# FTDI.net
KiCad netlist of a schematic drawn in Altium Designer
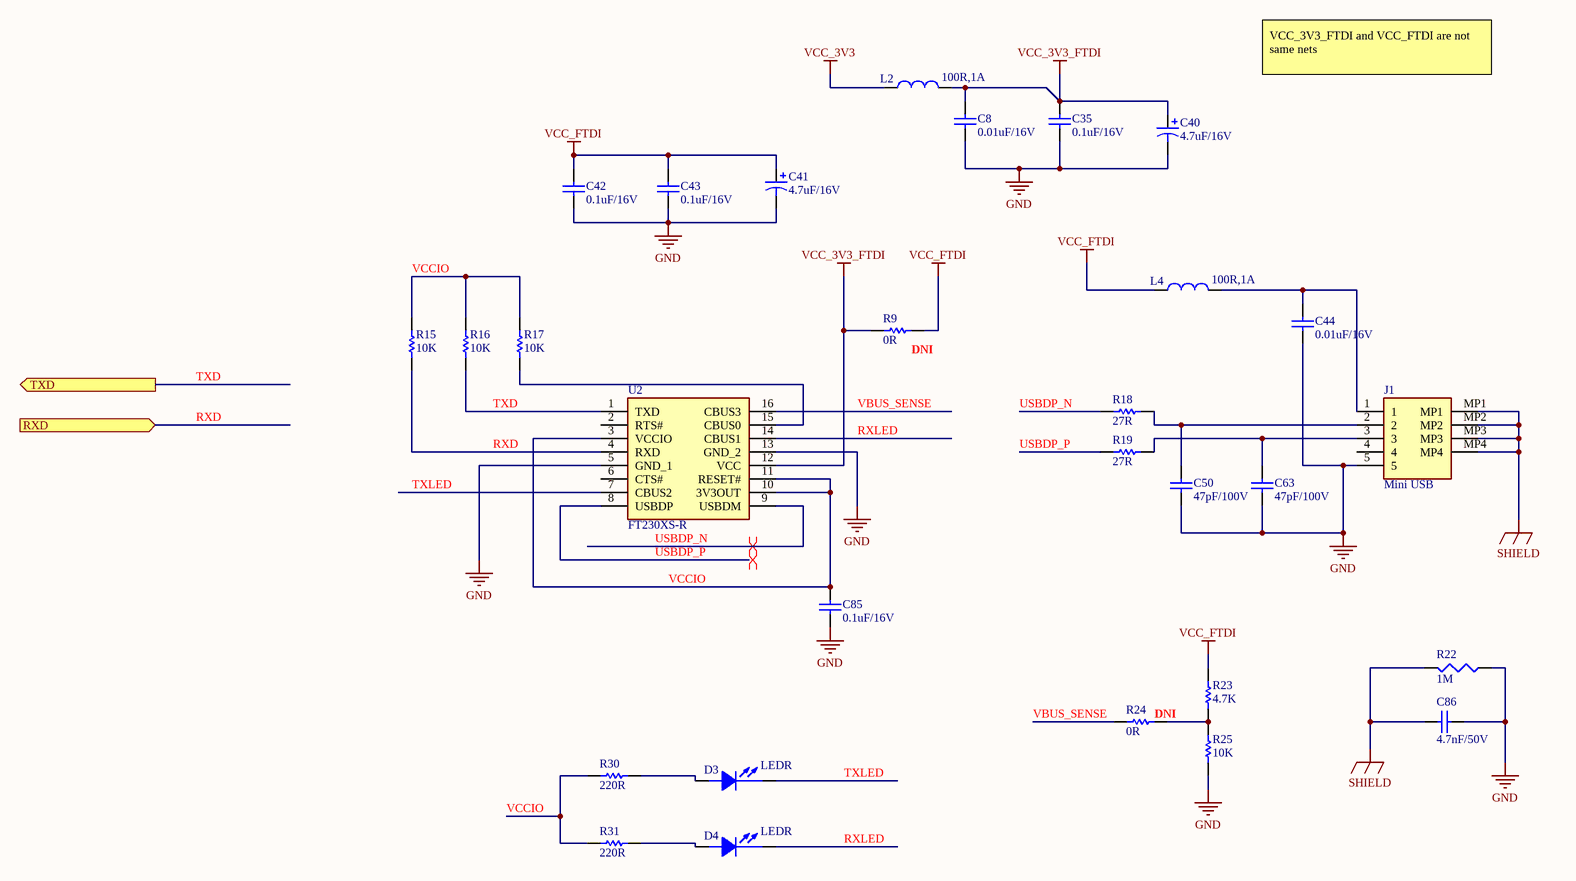
[diagram p0: FTDI.SchDoc]

(export (version "E")
  (design (tool "Eeschema 10.0.6"))
  (components
    (comp (ref "C8")
      (value "0.01uF/16V")
      (footprint "0603C")
      (description "Multilayer Ceramic Capacitors MLCC - SMD/SMT 16V 0.01uF X7R 0603 10% AEC-Q200")
      (fields (field (name "MFR") "KEMET") (field (name "MFR PART NO") "C0603C103K4RECAUTO"))
      (libsource (lib "Miscellaneous Devices") (part "Cap"))
    )
    (comp (ref "C35")
      (value "0.1uF/16V")
      (footprint "0603C")
      (description "Multilayer Ceramic Capacitors MLCC - SMD/SMT 0603 16VDC 0.1uF 10% X7R AEC-Q200")
      (fields (field (name "MFR") "Taiyo Yuden") (field (name "MFR PART NO") "EMK107B7104KAHT"))
      (libsource (lib "Miscellaneous Devices") (part "Cap"))
    )
    (comp (ref "C40")
      (value "4.7uF/16V")
      (footprint "CASE-A")
      (description "Tantalum Capacitors - Solid SMD 16V 4.7uF 1206")
      (fields (field (name "MFR") "KEMET") (field (name "MFR PART NO") "T495A475K016ATA2K0"))
      (libsource (lib "Miscellaneous Devices") (part "Cap Pol1"))
    )
    (comp (ref "C41")
      (value "4.7uF/16V")
      (footprint "CASE-A")
      (description "Tantalum Capacitors - Solid SMD 16V 4.7uF 1206")
      (fields (field (name "MFR") "KEMET") (field (name "MFR PART NO") "T495A475K016ATA2K0"))
      (libsource (lib "Miscellaneous Devices") (part "Cap Pol1"))
    )
    (comp (ref "C42")
      (value "0.1uF/16V")
      (footprint "0603C")
      (description "Multilayer Ceramic Capacitors MLCC - SMD/SMT 0603 16VDC 0.1uF 10% X7R AEC-Q2000")
      (fields (field (name "MFR") "Taiyo Yuden") (field (name "MFR PART NO") "EMK107B7104KAHT"))
      (libsource (lib "Miscellaneous Devices") (part "Cap"))
    )
    (comp (ref "C43")
      (value "0.1uF/16V")
      (footprint "0603C")
      (description "Multilayer Ceramic Capacitors MLCC - SMD/SMT 0603 16VDC 0.1uF 10% X7R AEC-Q2000")
      (fields (field (name "MFR") "Taiyo Yuden") (field (name "MFR PART NO") "EMK107B7104KAHT"))
      (libsource (lib "Miscellaneous Devices") (part "Cap"))
    )
    (comp (ref "C44")
      (value "0.01uF/16V")
      (footprint "0603C")
      (description "Multilayer Ceramic Capacitors MLCC - SMD/SMT 16V 0.01uF X7R 0603 10% AEC-Q200")
      (fields (field (name "MFR") "KEMET") (field (name "MFR PART NO") "C0603C103K4RECAUTO"))
      (libsource (lib "Miscellaneous Devices") (part "Cap"))
    )
    (comp (ref "C50")
      (value "47pF/100V")
      (footprint "0603C")
      (description "Multilayer Ceramic Capacitors MLCC - SMD/SMT 100V 47pF 0603 X8R 20% AEC-Q200")
      (fields (field (name "MFR") "KEMET") (field (name "MFR PART NO") "C0603C470M1HACAUTO"))
      (libsource (lib "Miscellaneous Devices") (part "Cap"))
    )
    (comp (ref "C63")
      (value "47pF/100V")
      (footprint "0603C")
      (description "Multilayer Ceramic Capacitors MLCC - SMD/SMT 100V 47pF 0603 X8R 20% AEC-Q200")
      (fields (field (name "MFR") "KEMET") (field (name "MFR PART NO") "C0603C470M1HACAUTO"))
      (libsource (lib "Miscellaneous Devices") (part "Cap"))
    )
    (comp (ref "C85")
      (value "0.1uF/16V")
      (footprint "0603C")
      (description "Multilayer Ceramic Capacitors MLCC - SMD/SMT 0603 16VDC 0.1uF 10% X7R AEC-Q2000")
      (fields (field (name "MFR") "Taiyo Yuden") (field (name "MFR PART NO") "EMK107B7104KAHT"))
      (libsource (lib "Miscellaneous Devices") (part "Cap"))
    )
    (comp (ref "C86")
      (value "4.7nF/50V")
      (footprint "0603C")
      (description "Multilayer Ceramic Capacitors MLCC - SMD/SMT 50V 4700pF X7R 0603 10% AEC-Q200")
      (fields
        (field (name "MFR PART NO") "C0603C472K5RACAUTO7411")
        (field (name "STOCKIEST PART NO") "80-C0603C472K5RAUTLR")
      )
      (libsource (lib "Myde10") (part "0805_CAP"))
    )
    (comp (ref "D3")
      (value "LEDR")
      (footprint "LED_0603")
      (description "Standard LEDs - SMD Red 631nm 14mcd 5mA")
      (fields
        (field (name "STOCKIEST PART NO") "859-LTSTC193KRKT5A")
        (field (name "MFR PART NO") "LTST-C193KRKT-5A")
      )
      (libsource (lib "de20") (part "LED"))
    )
    (comp (ref "D4")
      (value "LEDR")
      (footprint "LED_0603")
      (description "Standard LEDs - SMD Red 631nm 14mcd 5mA")
      (fields
        (field (name "STOCKIEST PART NO") "859-LTSTC193KRKT5A")
        (field (name "MFR PART NO") "LTST-C193KRKT-5A")
      )
      (libsource (lib "de20") (part "LED"))
    )
    (comp (ref "J1")
      (value "Mini USB")
      (footprint "ProjCLib:10033527-N3112LF")
      (description "USB Connectors M-USB 1X1 B/REC R/A SMT")
      (fields (field (name "MFR") "TE Connectivity") (field (name "MFR PART NO") "1734035-2"))
      (libsource (lib "*") (part "10033527-N3112LF"))
    )
    (comp (ref "L2")
      (value "100R,1A")
      (footprint "0603L")
      (description "Ferrite Beads 100ohms 1A 60mOhms 0603 Ferrite Chip")
      (fields (field (name "MFR") "TDK") (field (name "MFR PART NO") "MPZ1608D101BTA00"))
      (libsource (lib "de20") (part "0805_IND"))
    )
    (comp (ref "L4")
      (value "100R,1A")
      (footprint "0603L")
      (description "Ferrite Beads 100ohms 1A 60mOhms 0603 Ferrite Chip")
      (fields (field (name "MFR") "TDK") (field (name "MFR PART NO") "MPZ1608D101BTA00"))
      (libsource (lib "de20") (part "0805_IND"))
    )
    (comp (ref "R9")
      (value "0R")
      (footprint "0603R")
      (description "Thick Film Resistors - SMD 1/10Watt 0ohms Commercial Use")
      (fields (field (name "MFR") "Vishay / Dale") (field (name "MFR PART NO") "CRCW06030000Z0EAC"))
      (libsource (lib "Miscellaneous Devices") (part "Res1"))
    )
    (comp (ref "R15")
      (value "10K")
      (footprint "0603R")
      (description "Thick Film Resistors - SMD 0603 10Kohms 1% Anti-Sulfur AEC-Q200")
      (fields (field (name "MFR") "ROHM Semiconductor") (field (name "MFR PART NO") "SFR03EZPF1002"))
      (libsource (lib "Miscellaneous Devices") (part "Res1"))
    )
    (comp (ref "R16")
      (value "10K")
      (footprint "0603R")
      (description "Thick Film Resistors - SMD 0603 10Kohms 1% Anti-Sulfur AEC-Q200")
      (fields (field (name "MFR") "ROHM Semiconductor") (field (name "MFR PART NO") "SFR03EZPF1002"))
      (libsource (lib "Miscellaneous Devices") (part "Res1"))
    )
    (comp (ref "R17")
      (value "10K")
      (footprint "0603R")
      (description "Thick Film Resistors - SMD 0603 10Kohms 1% Anti-Sulfur AEC-Q200")
      (fields (field (name "MFR") "ROHM Semiconductor") (field (name "MFR PART NO") "SFR03EZPF1002"))
      (libsource (lib "Miscellaneous Devices") (part "Res1"))
    )
    (comp (ref "R18")
      (value "27R")
      (footprint "0603R")
      (description "Thick Film Resistors - SMD 0603 0.25W 1% 27ohm AEC-Q200")
      (fields (field (name "MFR") "Panasonic") (field (name "MFR PART NO") "ERJ-UP3F27R0V"))
      (libsource (lib "Miscellaneous Devices") (part "Res1"))
    )
    (comp (ref "R19")
      (value "27R")
      (footprint "0603R")
      (description "Thick Film Resistors - SMD 0603 0.25W 1% 27ohm AEC-Q200")
      (fields (field (name "MFR") "Panasonic") (field (name "MFR PART NO") "ERJ-UP3F27R0V"))
      (libsource (lib "Miscellaneous Devices") (part "Res1"))
    )
    (comp (ref "R22")
      (value "1M")
      (footprint "0805R")
      (description "Thick Film Resistors - SMD 0603 0.25W 1% 1Mohm AEC-Q200")
      (fields
        (field (name "MFR PART NO") "ERJ-UP3F1004V")
        (field (name "STOCKIEST PART NO") "667-ERJ-UP3F1004V")
      )
      (libsource (lib "Myde10") (part "0805_RES"))
    )
    (comp (ref "R23")
      (value "4.7K")
      (footprint "0603R")
      (description "Thick Film Resistors - SMD 1/10Watt 4.7Kohms 5% Commercial Use")
      (fields (field (name "MFR") "Vishay / Dale") (field (name "MFR PART NO") "CRCW06034K70JNEAC"))
      (libsource (lib "Miscellaneous Devices") (part "Res1"))
    )
    (comp (ref "R24")
      (value "0R")
      (footprint "0603R")
      (description "Thick Film Resistors - SMD 1/10Watt 0ohms Commercial Use")
      (fields (field (name "MFR") "Vishay / Dale") (field (name "MFR PART NO") "CRCW06030000Z0EAC"))
      (libsource (lib "Miscellaneous Devices") (part "Res1"))
    )
    (comp (ref "R25")
      (value "10K")
      (footprint "0603R")
      (description "Thick Film Resistors - SMD 0603 10Kohms 1% Anti-Sulfur AEC-Q200")
      (fields (field (name "MFR") "ROHM Semiconductor") (field (name "MFR PART NO") "SFR03EZPF1002"))
      (libsource (lib "Miscellaneous Devices") (part "Res1"))
    )
    (comp (ref "R30")
      (value "220R")
      (footprint "0603R")
      (description "Thick Film Resistors - SMD 1/10Watt 220ohms 5% Commercial Use")
      (fields (field (name "MFR") "Vishay / Dale") (field (name "MFR PART NO") "CRCW0603220RJNEAC"))
      (libsource (lib "Miscellaneous Devices") (part "Res1"))
    )
    (comp (ref "R31")
      (value "220R")
      (footprint "0603R")
      (description "Thick Film Resistors - SMD 1/10Watt 220ohms 5% Commercial Use")
      (fields (field (name "MFR") "Vishay / Dale") (field (name "MFR PART NO") "CRCW0603220RJNEAC"))
      (libsource (lib "Miscellaneous Devices") (part "Res1"))
    )
    (comp (ref "U2")
      (value "FT230XS-R")
      (footprint "FT230")
      (description "USB Interface IC USB to Basic Serial UART IC SSOP-16")
      (fields (field (name "MFR") "FTDI") (field (name "STOCKIEST PART NO") "895-FT230XS-R"))
      (libsource (lib "*") (part "FT230"))
    )
  )
  (nets
    (net (code "1") (name "/RXD") (class "Default")
      (node (ref "R15") (pin "2") (pinfunction "2_2") (pintype "passive"))
      (node (ref "U2") (pin "4") (pinfunction "RXD_4") (pintype "passive"))
    )
    (net (code "2") (name "/RXLED") (class "Default")
      (node (ref "D4") (pin "2") (pinfunction "CATHODE_2") (pintype "passive"))
      (node (ref "U2") (pin "14") (pinfunction "CBUS1_14") (pintype "passive"))
    )
    (net (code "3") (name "/TXD") (class "Default")
      (node (ref "R16") (pin "2") (pinfunction "2_2") (pintype "passive"))
      (node (ref "U2") (pin "1") (pinfunction "TXD_1") (pintype "passive"))
    )
    (net (code "4") (name "/TXLED") (class "Default")
      (node (ref "D3") (pin "2") (pinfunction "CATHODE_2") (pintype "passive"))
      (node (ref "U2") (pin "7") (pinfunction "CBUS2_7") (pintype "passive"))
    )
    (net (code "5") (name "/USBDP_N") (class "Default")
      (node (ref "R18") (pin "2") (pinfunction "2_2") (pintype "passive"))
      (node (ref "U2") (pin "9") (pinfunction "USBDM_9") (pintype "passive"))
    )
    (net (code "6") (name "/USBDP_P") (class "Default")
      (node (ref "R19") (pin "2") (pinfunction "2_2") (pintype "passive"))
      (node (ref "U2") (pin "8") (pinfunction "USBDP_8") (pintype "passive"))
    )
    (net (code "7") (name "/VBUS_SENSE") (class "Default")
      (node (ref "R24") (pin "1") (pinfunction "1_1") (pintype "passive"))
      (node (ref "U2") (pin "16") (pinfunction "CBUS3_16") (pintype "passive"))
    )
    (net (code "8") (name "/VCCIO") (class "Default")
      (node (ref "C85") (pin "2") (pinfunction "2_2") (pintype "passive"))
      (node (ref "R15") (pin "1") (pinfunction "1_1") (pintype "passive"))
      (node (ref "R16") (pin "1") (pinfunction "1_1") (pintype "passive"))
      (node (ref "R17") (pin "1") (pinfunction "1_1") (pintype "passive"))
      (node (ref "R30") (pin "2") (pinfunction "2_2") (pintype "passive"))
      (node (ref "R31") (pin "2") (pinfunction "2_2") (pintype "passive"))
      (node (ref "U2") (pin "10") (pinfunction "3V3OUT_10") (pintype "passive"))
      (node (ref "U2") (pin "11") (pinfunction "RESET#_11") (pintype "passive"))
      (node (ref "U2") (pin "3") (pinfunction "VCCIO_3") (pintype "passive"))
    )
    (net (code "9") (name "GND") (class "Default")
      (node (ref "C35") (pin "2") (pinfunction "2_2") (pintype "passive"))
      (node (ref "C40") (pin "2") (pinfunction "2_2") (pintype "passive"))
      (node (ref "C41") (pin "2") (pinfunction "2_2") (pintype "passive"))
      (node (ref "C42") (pin "1") (pinfunction "1_1") (pintype "passive"))
      (node (ref "C43") (pin "1") (pinfunction "1_1") (pintype "passive"))
      (node (ref "C44") (pin "2") (pinfunction "2_2") (pintype "passive"))
      (node (ref "C50") (pin "1") (pinfunction "1_1") (pintype "passive"))
      (node (ref "C63") (pin "1") (pinfunction "1_1") (pintype "passive"))
      (node (ref "C8") (pin "2") (pinfunction "2_2") (pintype "passive"))
      (node (ref "C85") (pin "1") (pinfunction "1_1") (pintype "passive"))
      (node (ref "C86") (pin "1") (pinfunction "1_1") (pintype "passive"))
      (node (ref "J1") (pin "5") (pinfunction "5_5") (pintype "passive"))
      (node (ref "R22") (pin "2") (pinfunction "2_2") (pintype "passive"))
      (node (ref "R25") (pin "2") (pinfunction "2_2") (pintype "passive"))
      (node (ref "U2") (pin "13") (pinfunction "GND_2_13") (pintype "passive"))
      (node (ref "U2") (pin "5") (pinfunction "GND_1_5") (pintype "passive"))
    )
    (net (code "10") (name "Net-(C44-Pad1)") (class "Default")
      (node (ref "C44") (pin "1") (pinfunction "1_1") (pintype "passive"))
      (node (ref "J1") (pin "1") (pinfunction "1_1") (pintype "passive"))
      (node (ref "L4") (pin "2") (pinfunction "2_2") (pintype "passive"))
    )
    (net (code "11") (name "Net-(C50-Pad2)") (class "Default")
      (node (ref "C50") (pin "2") (pinfunction "2_2") (pintype "passive"))
      (node (ref "J1") (pin "2") (pinfunction "2_2") (pintype "passive"))
      (node (ref "R18") (pin "1") (pinfunction "1_1") (pintype "passive"))
    )
    (net (code "12") (name "Net-(C63-Pad2)") (class "Default")
      (node (ref "C63") (pin "2") (pinfunction "2_2") (pintype "passive"))
      (node (ref "J1") (pin "3") (pinfunction "3_3") (pintype "passive"))
      (node (ref "R19") (pin "1") (pinfunction "1_1") (pintype "passive"))
    )
    (net (code "13") (name "Net-(D3-ANODE)") (class "Default")
      (node (ref "D3") (pin "1") (pinfunction "ANODE_1") (pintype "passive"))
      (node (ref "R30") (pin "1") (pinfunction "1_1") (pintype "passive"))
    )
    (net (code "14") (name "Net-(D4-ANODE)") (class "Default")
      (node (ref "D4") (pin "1") (pinfunction "ANODE_1") (pintype "passive"))
      (node (ref "R31") (pin "1") (pinfunction "1_1") (pintype "passive"))
    )
    (net (code "15") (name "Net-(R23-Pad1)") (class "Default")
      (node (ref "R23") (pin "1") (pinfunction "1_1") (pintype "passive"))
      (node (ref "R24") (pin "2") (pinfunction "2_2") (pintype "passive"))
      (node (ref "R25") (pin "1") (pinfunction "1_1") (pintype "passive"))
    )
    (net (code "16") (name "Net-(U2-CBUS0)") (class "Default")
      (node (ref "R17") (pin "2") (pinfunction "2_2") (pintype "passive"))
      (node (ref "U2") (pin "15") (pinfunction "CBUS0_15") (pintype "passive"))
    )
    (net (code "17") (name "SHIELD") (class "Default")
      (node (ref "C86") (pin "2") (pinfunction "2_2") (pintype "passive"))
      (node (ref "J1") (pin "MP1") (pinfunction "MP1_MP1") (pintype "passive"))
      (node (ref "J1") (pin "MP2") (pinfunction "MP2_MP2") (pintype "passive"))
      (node (ref "J1") (pin "MP3") (pinfunction "MP3_MP3") (pintype "passive"))
      (node (ref "J1") (pin "MP4") (pinfunction "MP4_MP4") (pintype "passive"))
      (node (ref "R22") (pin "1") (pinfunction "1_1") (pintype "passive"))
    )
    (net (code "18") (name "VCC_3V3") (class "Default")
      (node (ref "L2") (pin "1") (pinfunction "1_1") (pintype "passive"))
    )
    (net (code "19") (name "VCC_3V3_FTDI") (class "Default")
      (node (ref "C35") (pin "1") (pinfunction "1_1") (pintype "passive"))
      (node (ref "C40") (pin "1") (pinfunction "1_1") (pintype "passive"))
      (node (ref "C8") (pin "1") (pinfunction "1_1") (pintype "passive"))
      (node (ref "L2") (pin "2") (pinfunction "2_2") (pintype "passive"))
      (node (ref "R9") (pin "1") (pinfunction "1_1") (pintype "passive"))
      (node (ref "U2") (pin "12") (pinfunction "VCC_12") (pintype "passive"))
    )
    (net (code "20") (name "VCC_FTDI") (class "Default")
      (node (ref "C41") (pin "1") (pinfunction "1_1") (pintype "passive"))
      (node (ref "C42") (pin "2") (pinfunction "2_2") (pintype "passive"))
      (node (ref "C43") (pin "2") (pinfunction "2_2") (pintype "passive"))
      (node (ref "L4") (pin "1") (pinfunction "1_1") (pintype "passive"))
      (node (ref "R23") (pin "2") (pinfunction "2_2") (pintype "passive"))
      (node (ref "R9") (pin "2") (pinfunction "2_2") (pintype "passive"))
    )
    (net (code "21") (name "unconnected-(J1-Pad4)") (class "Default")
      (node (ref "J1") (pin "4") (pinfunction "4_4") (pintype "passive"))
    )
    (net (code "22") (name "unconnected-(U2-CTS#-Pad6)") (class "Default")
      (node (ref "U2") (pin "6") (pinfunction "CTS#_6") (pintype "passive"))
    )
    (net (code "23") (name "unconnected-(U2-RTS#-Pad2)") (class "Default")
      (node (ref "U2") (pin "2") (pinfunction "RTS#_2") (pintype "passive"))
    )
  )
)
